# mp3431-boost-tester-mk-1_1.net
KiCad netlist of a schematic drawn in EAGLE
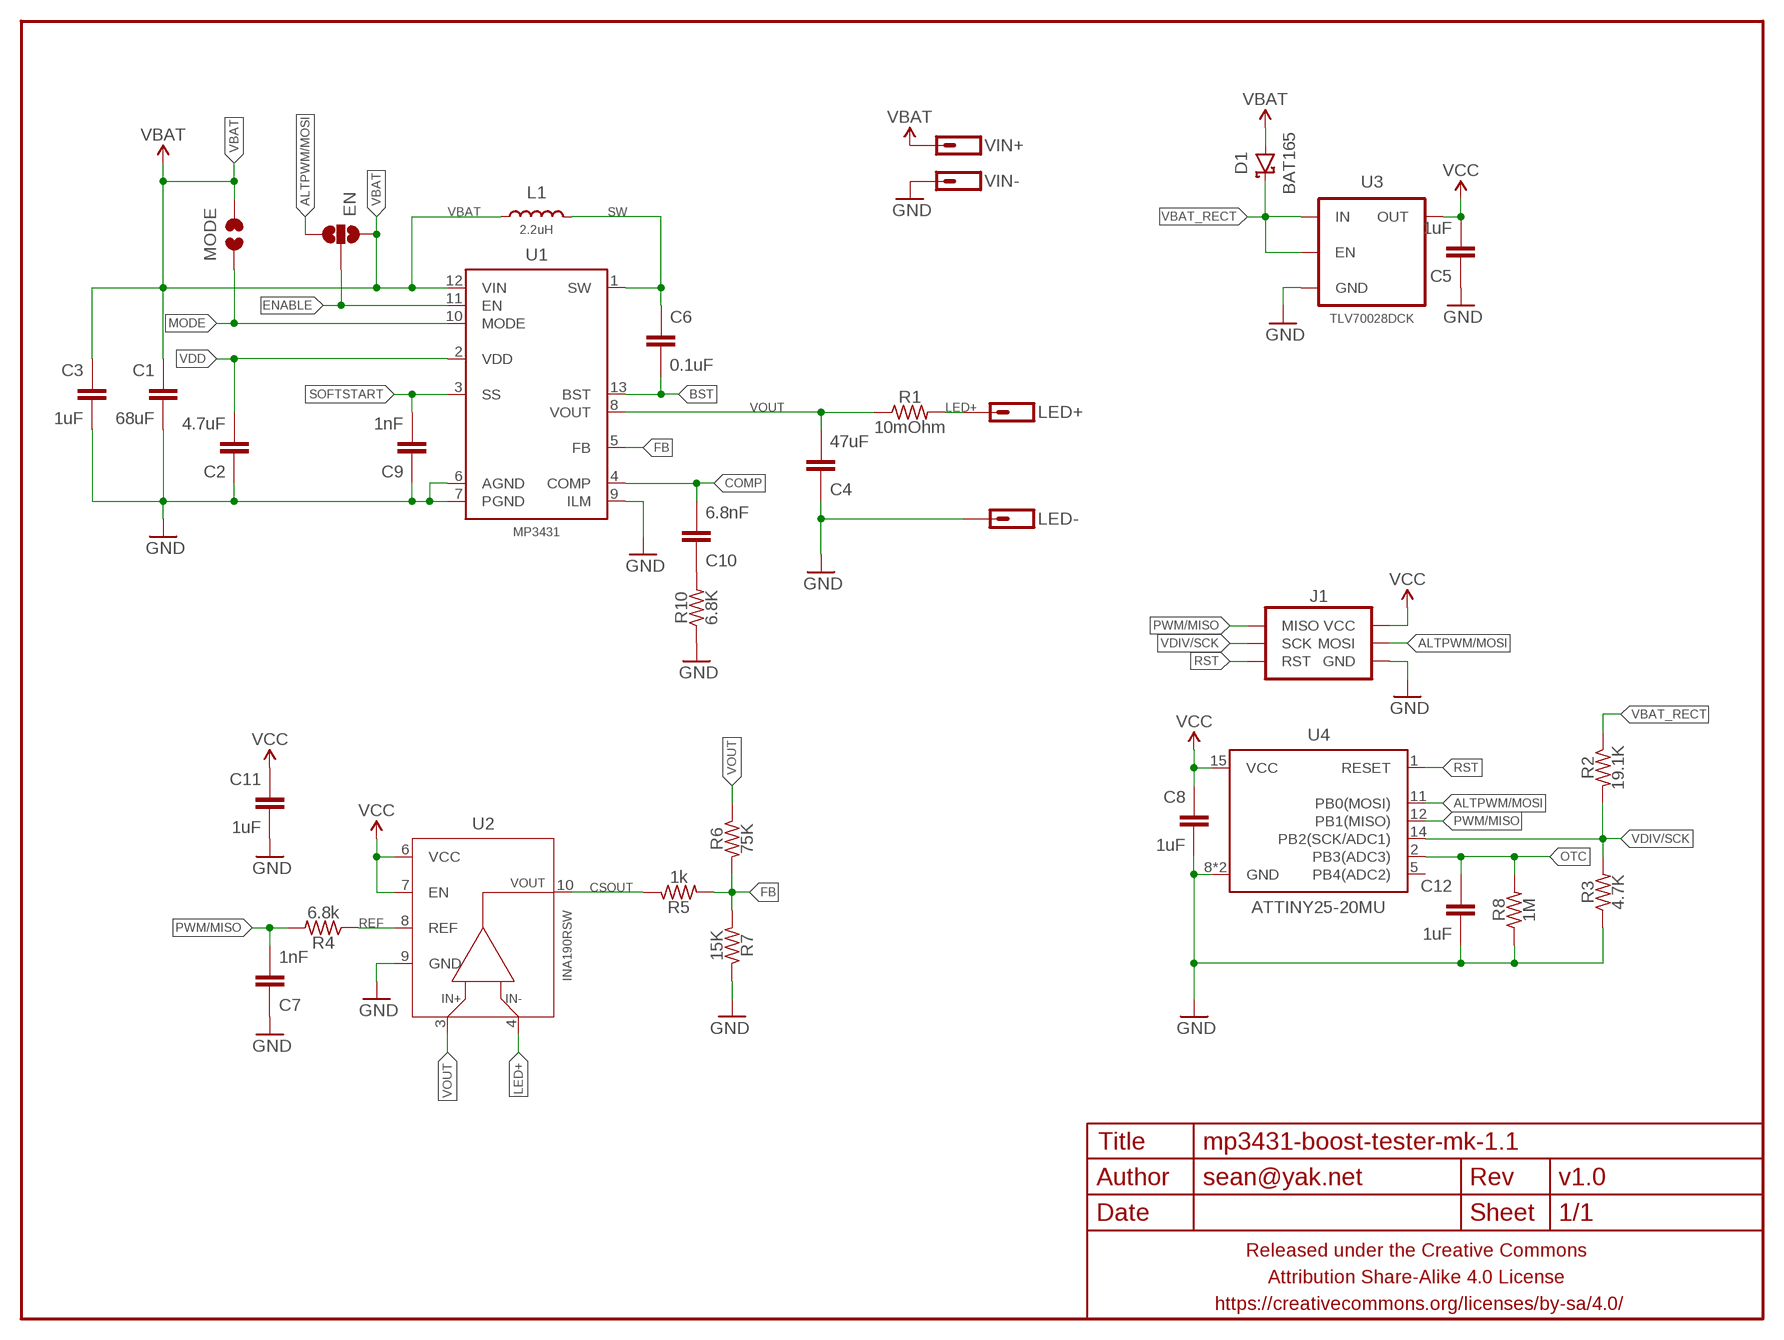
[diagram p0: schematic, sheet 1]

(export (version "E")
  (design (tool "Eeschema 10.0.6"))
  (components
    (comp (ref "C1")
      (value "68uF")
      (footprint "eagle-import:C1210")
      (libsource (lib "eagle-import") (part "CAPACITOR-CERAMICC1210"))
    )
    (comp (ref "C2")
      (value "4.7uF")
      (footprint "eagle-import:C0402")
      (libsource (lib "eagle-import") (part "CAPACITOR-CERAMICC0402"))
    )
    (comp (ref "C3")
      (value "1uF")
      (footprint "eagle-import:C0402")
      (libsource (lib "eagle-import") (part "CAPACITOR-CERAMICC0402"))
    )
    (comp (ref "C4")
      (value "47uF")
      (footprint "eagle-import:C1210")
      (libsource (lib "eagle-import") (part "CAPACITOR-CERAMICC1210"))
    )
    (comp (ref "C5")
      (value "1uF")
      (footprint "eagle-import:C0402")
      (libsource (lib "eagle-import") (part "CAPACITOR-CERAMICC0402"))
    )
    (comp (ref "C6")
      (value "0.1uF")
      (footprint "eagle-import:C0402")
      (libsource (lib "eagle-import") (part "CAPACITOR-CERAMICC0402"))
    )
    (comp (ref "C7")
      (value "1nF")
      (footprint "eagle-import:C0402")
      (libsource (lib "eagle-import") (part "CAPACITOR-CERAMICC0402"))
    )
    (comp (ref "C8")
      (value "1uF")
      (footprint "eagle-import:C0402")
      (libsource (lib "eagle-import") (part "CAPACITOR-CERAMICC0402"))
    )
    (comp (ref "C9")
      (value "1nF")
      (footprint "eagle-import:C0402")
      (libsource (lib "eagle-import") (part "CAPACITOR-CERAMICC0402"))
    )
    (comp (ref "C10")
      (value "6.8nF")
      (footprint "eagle-import:C0402")
      (libsource (lib "eagle-import") (part "CAPACITOR-CERAMICC0402"))
    )
    (comp (ref "C11")
      (value "1uF")
      (footprint "eagle-import:C0402")
      (libsource (lib "eagle-import") (part "CAPACITOR-CERAMICC0402"))
    )
    (comp (ref "C12")
      (value "1uF")
      (footprint "eagle-import:C0402")
      (libsource (lib "eagle-import") (part "CAPACITOR-CERAMICC0402"))
    )
    (comp (ref "D1")
      (value "BAT165")
      (footprint "eagle-import:SOD323-SCHOTTKY")
      (libsource (lib "eagle-import") (part "DIODE-SCHOTTKYSOD323"))
    )
    (comp (ref "EN")
      (value "JUMPER-PAD-3-NOSMALL_BOX_SILK")
      (footprint "eagle-import:PAD-JUMPER-3-NO_YES_SILK_SMALL_BOX")
      (libsource (lib "eagle-import") (part "JUMPER-PAD-3-NOSMALL_BOX_SILK"))
    )
    (comp (ref "FRAME1")
      (value "FRAME-LETTERNO_PACKAGE")
      (footprint "eagle-import:DUMMY")
      (fields
        (field (name "DESIGNER") "sean@yak.net")
        (field (name "VERSION") "v1.0")
        (field (name "DESIGNER_1") "sean@yak.net")
        (field (name "VERSION_1") "v1.0")
      )
      (libsource (lib "eagle-import") (part "FRAME-LETTERNO_PACKAGE"))
    )
    (comp (ref "J1")
      (value "AVR_SPI_PRG_6PTH")
      (footprint "eagle-import:2X3")
      (libsource (lib "eagle-import") (part "AVR_SPI_PRG_6PTH"))
    )
    (comp (ref "L1")
      (value "2.2uH")
      (footprint "eagle-import:XAL7070")
      (libsource (lib "eagle-import") (part "INDUCTORXAL7070"))
    )
    (comp (ref "LED+")
      (value "M01PTH-1.2MM-NS")
      (footprint "eagle-import:1X01-1.2MM-NS")
      (libsource (lib "eagle-import") (part "M01PTH-1.2MM-NS"))
    )
    (comp (ref "LED-")
      (value "M01PTH-1.2MM-NS")
      (footprint "eagle-import:1X01-1.2MM-NS")
      (libsource (lib "eagle-import") (part "M01PTH-1.2MM-NS"))
    )
    (comp (ref "MODE")
      (value "JUMPER-PAD-2-NOYES_SILK")
      (footprint "eagle-import:PAD-JUMPER-2-NO_YES_SILK")
      (libsource (lib "eagle-import") (part "JUMPER-PAD-2-NOYES_SILK"))
    )
    (comp (ref "R1")
      (value "10mOhm")
      (footprint "eagle-import:R1206")
      (libsource (lib "eagle-import") (part "RESISTORR1206"))
    )
    (comp (ref "R2")
      (value "19.1K")
      (footprint "eagle-import:R0402")
      (libsource (lib "eagle-import") (part "RESISTORR0402"))
    )
    (comp (ref "R3")
      (value "4.7K")
      (footprint "eagle-import:R0402")
      (libsource (lib "eagle-import") (part "RESISTORR0402"))
    )
    (comp (ref "R4")
      (value "6.8k")
      (footprint "eagle-import:R0402")
      (libsource (lib "eagle-import") (part "RESISTORR0402"))
    )
    (comp (ref "R5")
      (value "1k")
      (footprint "eagle-import:R0402")
      (libsource (lib "eagle-import") (part "RESISTORR0402"))
    )
    (comp (ref "R6")
      (value "75K")
      (footprint "eagle-import:R0402")
      (libsource (lib "eagle-import") (part "RESISTORR0402"))
    )
    (comp (ref "R7")
      (value "15K")
      (footprint "eagle-import:R0402")
      (libsource (lib "eagle-import") (part "RESISTORR0402"))
    )
    (comp (ref "R8")
      (value "1M")
      (footprint "eagle-import:R0402")
      (libsource (lib "eagle-import") (part "RESISTORR0402"))
    )
    (comp (ref "R10")
      (value "6.8K")
      (footprint "eagle-import:R0402")
      (libsource (lib "eagle-import") (part "RESISTORR0402"))
    )
    (comp (ref "U1")
      (value "MP3431")
      (footprint "eagle-import:MP3431")
      (libsource (lib "eagle-import") (part "MP3431"))
    )
    (comp (ref "U2")
      (value "INA190RSW")
      (footprint "eagle-import:UQFN-10")
      (libsource (lib "eagle-import") (part "INA190RSW"))
    )
    (comp (ref "U3")
      (value "TLV70028DCK")
      (footprint "eagle-import:SC70")
      (libsource (lib "eagle-import") (part "V_REG_ENTLV700XXDCR"))
    )
    (comp (ref "U4")
      (value "ATTINY25-20MU")
      (footprint "eagle-import:QFN20")
      (libsource (lib "eagle-import") (part "ATTINY45TINY85-20-QFN"))
    )
    (comp (ref "VIN+")
      (value "M01PTH-1.2MM-NS")
      (footprint "eagle-import:1X01-1.2MM-NS")
      (libsource (lib "eagle-import") (part "M01PTH-1.2MM-NS"))
    )
    (comp (ref "VIN-")
      (value "M01PTH-1.2MM-NS")
      (footprint "eagle-import:1X01-1.2MM-NS")
      (libsource (lib "eagle-import") (part "M01PTH-1.2MM-NS"))
    )
  )
  (nets
    (net (code "1") (name "/CSOUT") (class "Default")
      (node (ref "R5") (pin "1") (pinfunction "1_1") (pintype "passive"))
      (node (ref "U2") (pin "10") (pinfunction "OUT_10") (pintype "bidirectional"))
    )
    (net (code "2") (name "/REF") (class "Default")
      (node (ref "R4") (pin "1") (pinfunction "1_1") (pintype "passive"))
      (node (ref "U2") (pin "8") (pinfunction "REF_8") (pintype "bidirectional"))
    )
    (net (code "3") (name "/SW") (class "Default")
      (node (ref "C6") (pin "1") (pinfunction "1_1") (pintype "passive"))
      (node (ref "L1") (pin "P$2") (pinfunction "2_P$2") (pintype "passive"))
      (node (ref "U1") (pin "1") (pinfunction "SW_1") (pintype "bidirectional"))
    )
    (net (code "4") (name "ALTPWM{slash}MOSI") (class "Default")
      (node (ref "EN") (pin "3") (pinfunction "3_3") (pintype "passive"))
      (node (ref "J1") (pin "4") (pinfunction "MOSI_4") (pintype "passive"))
      (node (ref "U4") (pin "11") (pinfunction "PB0(MOSI)_11") (pintype "bidirectional"))
    )
    (net (code "5") (name "BST") (class "Default")
      (node (ref "C6") (pin "2") (pinfunction "2_2") (pintype "passive"))
      (node (ref "U1") (pin "13") (pinfunction "BST_13") (pintype "bidirectional"))
    )
    (net (code "6") (name "COMP") (class "Default")
      (node (ref "C10") (pin "2") (pinfunction "2_2") (pintype "passive"))
      (node (ref "U1") (pin "4") (pinfunction "COMP_4") (pintype "bidirectional"))
    )
    (net (code "7") (name "ENABLE") (class "Default")
      (node (ref "EN") (pin "2") (pinfunction "2_2") (pintype "passive"))
      (node (ref "U1") (pin "11") (pinfunction "EN_11") (pintype "bidirectional"))
    )
    (net (code "8") (name "FB") (class "Default")
      (node (ref "R5") (pin "2") (pinfunction "2_2") (pintype "passive"))
      (node (ref "R6") (pin "2") (pinfunction "2_2") (pintype "passive"))
      (node (ref "R7") (pin "2") (pinfunction "2_2") (pintype "passive"))
      (node (ref "U1") (pin "5") (pinfunction "FB_5") (pintype "bidirectional"))
    )
    (net (code "9") (name "GND") (class "Default")
      (node (ref "C1") (pin "2") (pinfunction "2_2") (pintype "passive"))
      (node (ref "C11") (pin "2") (pinfunction "2_2") (pintype "passive"))
      (node (ref "C12") (pin "2") (pinfunction "2_2") (pintype "passive"))
      (node (ref "C2") (pin "1") (pinfunction "1_1") (pintype "passive"))
      (node (ref "C3") (pin "2") (pinfunction "2_2") (pintype "passive"))
      (node (ref "C4") (pin "1") (pinfunction "1_1") (pintype "passive"))
      (node (ref "C5") (pin "1") (pinfunction "1_1") (pintype "passive"))
      (node (ref "C7") (pin "1") (pinfunction "1_1") (pintype "passive"))
      (node (ref "C8") (pin "2") (pinfunction "2_2") (pintype "passive"))
      (node (ref "C9") (pin "1") (pinfunction "1_1") (pintype "passive"))
      (node (ref "J1") (pin "6") (pinfunction "GND_6") (pintype "passive"))
      (node (ref "LED-") (pin "P$1") (pinfunction "1_P$1") (pintype "passive"))
      (node (ref "R10") (pin "1") (pinfunction "1_1") (pintype "passive"))
      (node (ref "R3") (pin "1") (pinfunction "1_1") (pintype "passive"))
      (node (ref "R7") (pin "1") (pinfunction "1_1") (pintype "passive"))
      (node (ref "R8") (pin "1") (pinfunction "1_1") (pintype "passive"))
      (node (ref "U1") (pin "6") (pinfunction "AGND_6") (pintype "bidirectional"))
      (node (ref "U1") (pin "7") (pinfunction "PGND_7") (pintype "bidirectional"))
      (node (ref "U1") (pin "9") (pinfunction "ILM_9") (pintype "bidirectional"))
      (node (ref "U2") (pin "9") (pinfunction "GND_9") (pintype "bidirectional"))
      (node (ref "U3") (pin "2") (pinfunction "GND_2") (pintype "input"))
      (node (ref "U4") (pin "8") (pinfunction "GND_8") (pintype "bidirectional"))
      (node (ref "U4") (pin "PAD") (pinfunction "GND_PAD") (pintype "bidirectional"))
      (node (ref "VIN-") (pin "P$1") (pinfunction "1_P$1") (pintype "passive"))
    )
    (net (code "10") (name "LED+") (class "Default")
      (node (ref "LED+") (pin "P$1") (pinfunction "1_P$1") (pintype "passive"))
      (node (ref "R1") (pin "2") (pinfunction "2_2") (pintype "passive"))
      (node (ref "U2") (pin "4") (pinfunction "VIN-_4") (pintype "bidirectional"))
    )
    (net (code "11") (name "MODE") (class "Default")
      (node (ref "MODE") (pin "1") (pinfunction "1_1") (pintype "passive"))
      (node (ref "U1") (pin "10") (pinfunction "MODE_10") (pintype "bidirectional"))
    )
    (net (code "12") (name "Net-(C10-Pad1)") (class "Default")
      (node (ref "C10") (pin "1") (pinfunction "1_1") (pintype "passive"))
      (node (ref "R10") (pin "2") (pinfunction "2_2") (pintype "passive"))
    )
    (net (code "13") (name "OTC") (class "Default")
      (node (ref "C12") (pin "1") (pinfunction "1_1") (pintype "passive"))
      (node (ref "R8") (pin "2") (pinfunction "2_2") (pintype "passive"))
      (node (ref "U4") (pin "2") (pinfunction "PB3(ADC3)_2") (pintype "bidirectional"))
    )
    (net (code "14") (name "PWM{slash}MISO") (class "Default")
      (node (ref "C7") (pin "2") (pinfunction "2_2") (pintype "passive"))
      (node (ref "J1") (pin "1") (pinfunction "MISO_1") (pintype "passive"))
      (node (ref "R4") (pin "2") (pinfunction "2_2") (pintype "passive"))
      (node (ref "U4") (pin "12") (pinfunction "PB1(MISO)_12") (pintype "bidirectional"))
    )
    (net (code "15") (name "RST") (class "Default")
      (node (ref "J1") (pin "5") (pinfunction "RST_5") (pintype "passive"))
      (node (ref "U4") (pin "1") (pinfunction "RESET_1") (pintype "bidirectional"))
    )
    (net (code "16") (name "SOFTSTART") (class "Default")
      (node (ref "C9") (pin "2") (pinfunction "2_2") (pintype "passive"))
      (node (ref "U1") (pin "3") (pinfunction "SS_3") (pintype "bidirectional"))
    )
    (net (code "17") (name "VBAT") (class "Default")
      (node (ref "C1") (pin "1") (pinfunction "1_1") (pintype "passive"))
      (node (ref "C3") (pin "1") (pinfunction "1_1") (pintype "passive"))
      (node (ref "D1") (pin "A") (pinfunction "A_A") (pintype "passive"))
      (node (ref "EN") (pin "1") (pinfunction "1_1") (pintype "passive"))
      (node (ref "L1") (pin "P$1") (pinfunction "1_P$1") (pintype "passive"))
      (node (ref "MODE") (pin "2") (pinfunction "2_2") (pintype "passive"))
      (node (ref "U1") (pin "12") (pinfunction "VIN_12") (pintype "bidirectional"))
      (node (ref "VIN+") (pin "P$1") (pinfunction "1_P$1") (pintype "passive"))
    )
    (net (code "18") (name "VBAT_RECT") (class "Default")
      (node (ref "D1") (pin "C") (pinfunction "C_C") (pintype "passive"))
      (node (ref "R2") (pin "1") (pinfunction "1_1") (pintype "passive"))
      (node (ref "U3") (pin "1") (pinfunction "IN_1") (pintype "input"))
      (node (ref "U3") (pin "3") (pinfunction "EN_3") (pintype "input"))
    )
    (net (code "19") (name "VCC") (class "Default")
      (node (ref "C11") (pin "1") (pinfunction "1_1") (pintype "passive"))
      (node (ref "C5") (pin "2") (pinfunction "2_2") (pintype "passive"))
      (node (ref "C8") (pin "1") (pinfunction "1_1") (pintype "passive"))
      (node (ref "J1") (pin "2") (pinfunction "VCC_2") (pintype "passive"))
      (node (ref "U2") (pin "6") (pinfunction "VCC_6") (pintype "bidirectional"))
      (node (ref "U2") (pin "7") (pinfunction "EN_7") (pintype "bidirectional"))
      (node (ref "U3") (pin "5") (pinfunction "OUT_5") (pintype "passive"))
      (node (ref "U4") (pin "15") (pinfunction "VCC_15") (pintype "bidirectional"))
    )
    (net (code "20") (name "VDD") (class "Default")
      (node (ref "C2") (pin "2") (pinfunction "2_2") (pintype "passive"))
      (node (ref "U1") (pin "2") (pinfunction "VDD_2") (pintype "bidirectional"))
    )
    (net (code "21") (name "VDIV{slash}SCK") (class "Default")
      (node (ref "J1") (pin "3") (pinfunction "SCK_3") (pintype "passive"))
      (node (ref "R2") (pin "2") (pinfunction "2_2") (pintype "passive"))
      (node (ref "R3") (pin "2") (pinfunction "2_2") (pintype "passive"))
      (node (ref "U4") (pin "14") (pinfunction "PB2(SCK/ADC1)_14") (pintype "bidirectional"))
    )
    (net (code "22") (name "VOUT") (class "Default")
      (node (ref "C4") (pin "2") (pinfunction "2_2") (pintype "passive"))
      (node (ref "R1") (pin "1") (pinfunction "1_1") (pintype "passive"))
      (node (ref "R6") (pin "1") (pinfunction "1_1") (pintype "passive"))
      (node (ref "U1") (pin "8") (pinfunction "VOUT_8") (pintype "bidirectional"))
      (node (ref "U2") (pin "3") (pinfunction "VIN+_3") (pintype "bidirectional"))
    )
    (net (code "23") (name "unconnected-(U4-PB4(ADC2)-Pad5)") (class "Default")
      (node (ref "U4") (pin "5") (pinfunction "PB4(ADC2)_5") (pintype "bidirectional"))
    )
  )
)
